# Universal_Remote.net
KiCad netlist of a schematic drawn in EAGLE
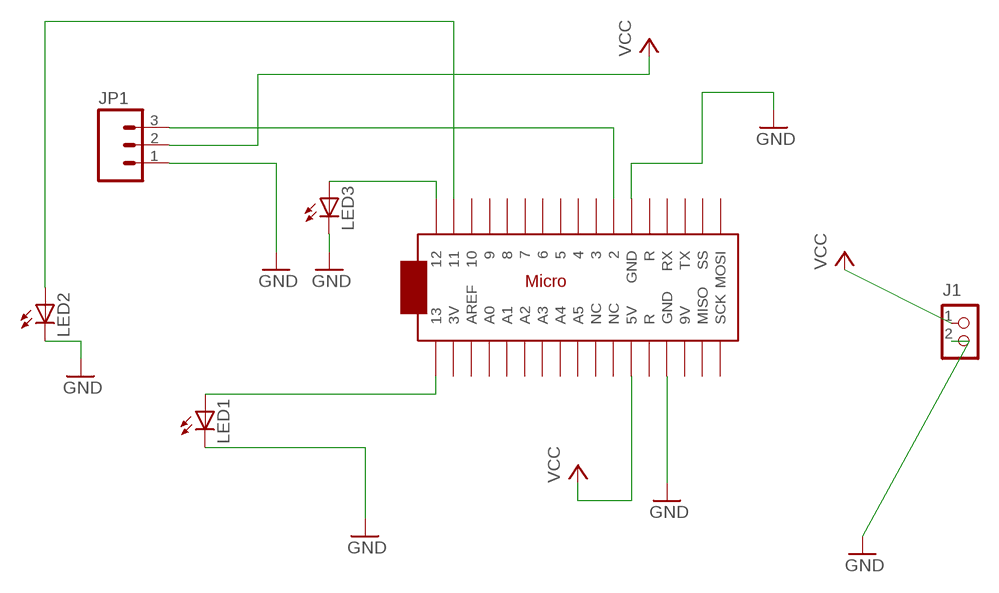
[diagram p0: schematic, sheet 1]

(export (version "E")
  (design (tool "Eeschema 10.0.6"))
  (components
    (comp (ref "J1")
      (value "CON_TERMINAL_BLOCK_02-5MM")
      (footprint "eagle-import:TERMINAL_BLOCK_2P_5")
      (libsource (lib "eagle-import") (part "CON_TERMINAL_BLOCK_02-5MM"))
    )
    (comp (ref "JP1")
      (value "M03JST-PTH-VERT")
      (footprint "eagle-import:JST-3-PTH-VERT")
      (libsource (lib "eagle-import") (part "M03JST-PTH-VERT"))
    )
    (comp (ref "LED1")
      (value "LED5MM")
      (footprint "eagle-import:LED5MM")
      (libsource (lib "eagle-import") (part "LED5MM"))
    )
    (comp (ref "LED2")
      (value "LED5MM")
      (footprint "eagle-import:LED5MM")
      (libsource (lib "eagle-import") (part "LED5MM"))
    )
    (comp (ref "LED3")
      (value "LED5MM")
      (footprint "eagle-import:LED5MM")
      (libsource (lib "eagle-import") (part "LED5MM"))
    )
    (comp (ref "U$1")
      (value "ARDUINOMICRO")
      (footprint "eagle-import:ARDUINOMICRO")
      (libsource (lib "eagle-import") (part "ARDUINOMICRO"))
    )
  )
  (nets
    (net (code "1") (name "GND") (class "Default")
      (node (ref "J1") (pin "2") (pinfunction "2_2") (pintype "passive"))
      (node (ref "JP1") (pin "1") (pinfunction "1_1") (pintype "passive"))
      (node (ref "LED1") (pin "K") (pinfunction "C_K") (pintype "passive"))
      (node (ref "LED2") (pin "K") (pinfunction "C_K") (pintype "passive"))
      (node (ref "LED3") (pin "K") (pinfunction "C_K") (pintype "passive"))
      (node (ref "U$1") (pin "P$12") (pinfunction "GND_P$12") (pintype "bidirectional"))
      (node (ref "U$1") (pin "P$21") (pinfunction "GND_P$21") (pintype "bidirectional"))
    )
    (net (code "2") (name "Net-(U$1-2)") (class "Default")
      (node (ref "JP1") (pin "3") (pinfunction "3_3") (pintype "passive"))
      (node (ref "U$1") (pin "P$11") (pinfunction "2_P$11") (pintype "bidirectional"))
    )
    (net (code "3") (name "Net-(U$1-11)") (class "Default")
      (node (ref "LED2") (pin "A") (pinfunction "A_A") (pintype "passive"))
      (node (ref "U$1") (pin "P$2") (pinfunction "11_P$2") (pintype "bidirectional"))
    )
    (net (code "4") (name "Net-(U$1-12)") (class "Default")
      (node (ref "LED3") (pin "A") (pinfunction "A_A") (pintype "passive"))
      (node (ref "U$1") (pin "P$1") (pinfunction "12_P$1") (pintype "bidirectional"))
    )
    (net (code "5") (name "Net-(U$1-13)") (class "Default")
      (node (ref "LED1") (pin "A") (pinfunction "A_A") (pintype "passive"))
      (node (ref "U$1") (pin "P$34") (pinfunction "13_P$34") (pintype "bidirectional"))
    )
    (net (code "6") (name "VCC") (class "Default")
      (node (ref "J1") (pin "1") (pinfunction "1_1") (pintype "passive"))
      (node (ref "JP1") (pin "2") (pinfunction "2_2") (pintype "passive"))
      (node (ref "U$1") (pin "P$23") (pinfunction "5V_P$23") (pintype "bidirectional"))
    )
    (net (code "7") (name "unconnected-(U$1-3-PadP$10)") (class "Default")
      (node (ref "U$1") (pin "P$10") (pinfunction "3_P$10") (pintype "bidirectional"))
    )
    (net (code "8") (name "unconnected-(U$1-3V-PadP$33)") (class "Default")
      (node (ref "U$1") (pin "P$33") (pinfunction "3V_P$33") (pintype "bidirectional"))
    )
    (net (code "9") (name "unconnected-(U$1-4-PadP$9)") (class "Default")
      (node (ref "U$1") (pin "P$9") (pinfunction "4_P$9") (pintype "bidirectional"))
    )
    (net (code "10") (name "unconnected-(U$1-5-PadP$8)") (class "Default")
      (node (ref "U$1") (pin "P$8") (pinfunction "5_P$8") (pintype "bidirectional"))
    )
    (net (code "11") (name "unconnected-(U$1-6-PadP$7)") (class "Default")
      (node (ref "U$1") (pin "P$7") (pinfunction "6_P$7") (pintype "bidirectional"))
    )
    (net (code "12") (name "unconnected-(U$1-7-PadP$6)") (class "Default")
      (node (ref "U$1") (pin "P$6") (pinfunction "7_P$6") (pintype "bidirectional"))
    )
    (net (code "13") (name "unconnected-(U$1-8-PadP$5)") (class "Default")
      (node (ref "U$1") (pin "P$5") (pinfunction "8_P$5") (pintype "bidirectional"))
    )
    (net (code "14") (name "unconnected-(U$1-9-PadP$4)") (class "Default")
      (node (ref "U$1") (pin "P$4") (pinfunction "9_P$4") (pintype "bidirectional"))
    )
    (net (code "15") (name "unconnected-(U$1-9V-PadP$20)") (class "Default")
      (node (ref "U$1") (pin "P$20") (pinfunction "9V_P$20") (pintype "bidirectional"))
    )
    (net (code "16") (name "unconnected-(U$1-10-PadP$3)") (class "Default")
      (node (ref "U$1") (pin "P$3") (pinfunction "10_P$3") (pintype "bidirectional"))
    )
    (net (code "17") (name "unconnected-(U$1-A0-PadP$31)") (class "Default")
      (node (ref "U$1") (pin "P$31") (pinfunction "A0_P$31") (pintype "bidirectional"))
    )
    (net (code "18") (name "unconnected-(U$1-A1-PadP$30)") (class "Default")
      (node (ref "U$1") (pin "P$30") (pinfunction "A1_P$30") (pintype "bidirectional"))
    )
    (net (code "19") (name "unconnected-(U$1-A2-PadP$29)") (class "Default")
      (node (ref "U$1") (pin "P$29") (pinfunction "A2_P$29") (pintype "bidirectional"))
    )
    (net (code "20") (name "unconnected-(U$1-A3-PadP$28)") (class "Default")
      (node (ref "U$1") (pin "P$28") (pinfunction "A3_P$28") (pintype "bidirectional"))
    )
    (net (code "21") (name "unconnected-(U$1-A4-PadP$27)") (class "Default")
      (node (ref "U$1") (pin "P$27") (pinfunction "A4_P$27") (pintype "bidirectional"))
    )
    (net (code "22") (name "unconnected-(U$1-A5-PadP$26)") (class "Default")
      (node (ref "U$1") (pin "P$26") (pinfunction "A5_P$26") (pintype "bidirectional"))
    )
    (net (code "23") (name "unconnected-(U$1-AREF-PadP$32)") (class "Default")
      (node (ref "U$1") (pin "P$32") (pinfunction "AREF_P$32") (pintype "bidirectional"))
    )
    (net (code "24") (name "unconnected-(U$1-MISO-PadP$19)") (class "Default")
      (node (ref "U$1") (pin "P$19") (pinfunction "MISO_P$19") (pintype "bidirectional"))
    )
    (net (code "25") (name "unconnected-(U$1-MOSI-PadP$17)") (class "Default")
      (node (ref "U$1") (pin "P$17") (pinfunction "MOSI_P$17") (pintype "bidirectional"))
    )
    (net (code "26") (name "unconnected-(U$1-NC-PadP$24)") (class "Default")
      (node (ref "U$1") (pin "P$24") (pinfunction "NC_P$24") (pintype "bidirectional"))
    )
    (net (code "27") (name "unconnected-(U$1-NC-PadP$25)") (class "Default")
      (node (ref "U$1") (pin "P$25") (pinfunction "NC_P$25") (pintype "bidirectional"))
    )
    (net (code "28") (name "unconnected-(U$1-R-PadP$13)") (class "Default")
      (node (ref "U$1") (pin "P$13") (pinfunction "R_P$13") (pintype "bidirectional"))
    )
    (net (code "29") (name "unconnected-(U$1-R-PadP$22)") (class "Default")
      (node (ref "U$1") (pin "P$22") (pinfunction "R_P$22") (pintype "bidirectional"))
    )
    (net (code "30") (name "unconnected-(U$1-RX-PadP$14)") (class "Default")
      (node (ref "U$1") (pin "P$14") (pinfunction "RX_P$14") (pintype "bidirectional"))
    )
    (net (code "31") (name "unconnected-(U$1-SCK-PadP$18)") (class "Default")
      (node (ref "U$1") (pin "P$18") (pinfunction "SCK_P$18") (pintype "bidirectional"))
    )
    (net (code "32") (name "unconnected-(U$1-SS-PadP$16)") (class "Default")
      (node (ref "U$1") (pin "P$16") (pinfunction "SS_P$16") (pintype "bidirectional"))
    )
    (net (code "33") (name "unconnected-(U$1-TX-PadP$15)") (class "Default")
      (node (ref "U$1") (pin "P$15") (pinfunction "TX_P$15") (pintype "bidirectional"))
    )
  )
)
